# Power_Driver_2.net
KiCad netlist of a schematic drawn in Altium Designer
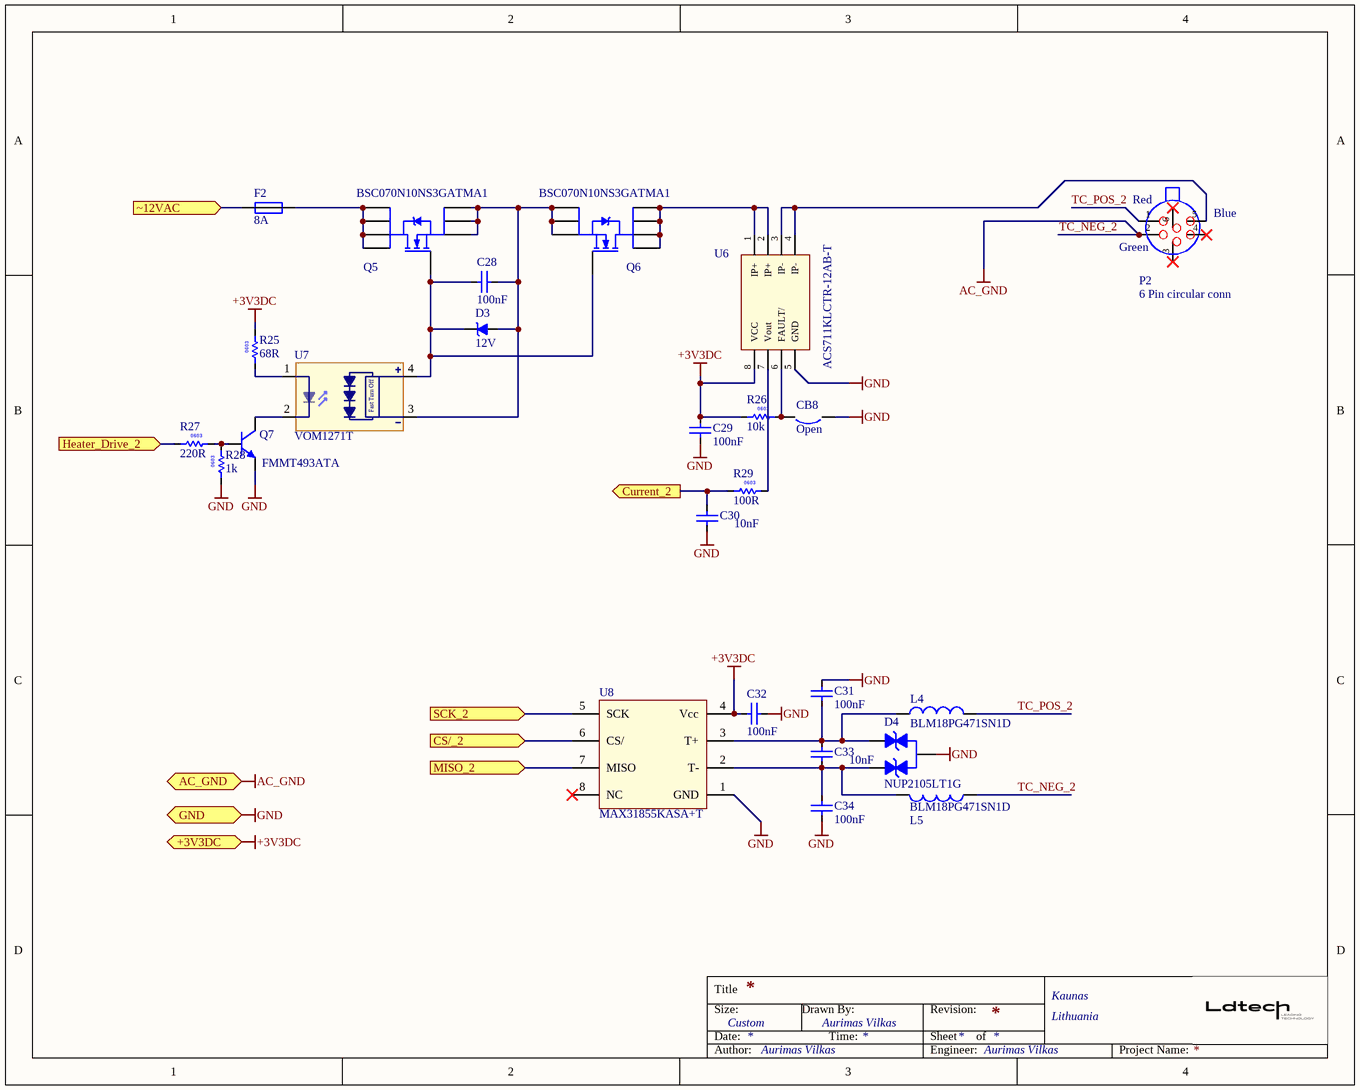
[diagram p0: Power_Driver_2.SchDoc]

(export (version "E")
  (design (tool "Eeschema 10.0.6"))
  (components
    (comp (ref "C28") (value "100nF") (footprint "CAPC1608N") (libsource (lib "DB") (part "C_SM")))
    (comp (ref "C29") (value "100nF") (footprint "CAPC1608N") (libsource (lib "DB") (part "C_SM")))
    (comp (ref "C30") (value "10nF") (footprint "CAPC1608N") (libsource (lib "DB") (part "C_SM")))
    (comp (ref "C31") (value "100nF") (footprint "CAPC1608N") (libsource (lib "DB") (part "C_SM")))
    (comp (ref "C32") (value "100nF") (footprint "CAPC1608N") (libsource (lib "DB") (part "C_SM")))
    (comp (ref "C33") (value "10nF") (footprint "CAPC1608N") (libsource (lib "DB") (part "C_SM")))
    (comp (ref "C34") (value "100nF") (footprint "CAPC1608N") (libsource (lib "DB") (part "C_SM")))
    (comp (ref "CB8")
      (value "Open")
      (footprint "CB_0603")
      (description "Circuit Breaker")
      (libsource (lib "AV_Lib_200418") (part "CB Open"))
    )
    (comp (ref "D3")
      (value "12V")
      (footprint "SOD-80C")
      (description "BZT55C12-GS08 -  Zener Single Diode, 12 V, 500 mW, SOD-80 (MiniMELF), 5 %, 2 Pins, 175 °C")
      (libsource (lib "AV_Lib_200418") (part "12V"))
    )
    (comp (ref "D4")
      (value "NUP2105LT1G")
      (footprint "SOT23-3")
      (description "NUP2105LT1G -  TVS Diode, NUP21 Series, Bidirectional, 22 V, 40 V, SOT-23, 3 Pins")
      (libsource (lib "AV_Lib_200418") (part "NUP2105LT1G"))
    )
    (comp (ref "F2")
      (value "8A")
      (footprint "1206F")
      (description "MCCFB1206TFF/8 -  Fuse, Surface Mount, 8 A, 32 V, Fast Acting, 1206")
      (libsource (lib "AV_Lib_200418") (part "8A Fuse"))
    )
    (comp (ref "L4")
      (value "BLM18PG471SN1D")
      (footprint "LL0603\\2P")
      (description "BLM18PG471SN1D -  Ferrite Bead, 0603 [1608 Metric], 470 ohm, 1 A, BLM18P Series, 0.2 ohm, ± 25%")
      (libsource (lib "DB") (part "L"))
    )
    (comp (ref "L5")
      (value "BLM18PG471SN1D")
      (footprint "LL0603\\2P")
      (description "BLM18PG471SN1D -  Ferrite Bead, 0603 [1608 Metric], 470 ohm, 1 A, BLM18P Series, 0.2 ohm, ± 25%")
      (libsource (lib "DB") (part "L"))
    )
    (comp (ref "P2")
      (value "6 Pin circular conn")
      (footprint "RPC1-12RB-6P(71)")
      (description "RPC1-12RB-6P(71) -  Circular Connector, RP Series, Panel Mount Receptacle, 6 Contacts, Solder Pin")
      (libsource (lib "AV_Lib_200418") (part "RPC1-12RB-6P(71)"))
    )
    (comp (ref "Q5")
      (value "BSC070N10NS3GATMA1")
      (footprint "PG-TDSON-8")
      (description "BSC070N10NS3GATMA1 -  Power MOSFET, N Channel, 100 V, 90 A, 0.0063 ohm, TDSON, Surface Mount")
      (libsource (lib "AV_Lib_200418") (part "BSC070N10NS3GATMA1"))
    )
    (comp (ref "Q6")
      (value "BSC070N10NS3GATMA1")
      (footprint "PG-TDSON-8")
      (description "BSC070N10NS3GATMA1 -  Power MOSFET, N Channel, 100 V, 90 A, 0.0063 ohm, TDSON, Surface Mount")
      (libsource (lib "AV_Lib_200418") (part "BSC070N10NS3GATMA1"))
    )
    (comp (ref "Q7")
      (value "FMMT493ATA")
      (footprint "SOT23-3")
      (description "FMMT493ATA -  Bipolar (BJT) Single Transistor, NPN, 60 V, 150 MHz, 500 mW, 1 A, 300 hFE")
      (libsource (lib "AV_Lib_200418") (part "FMMT493ATA"))
    )
    (comp (ref "R25") (value "68R") (footprint "RESC1608N") (libsource (lib "DB") (part "R0603")))
    (comp (ref "R26") (value "10k") (footprint "RESC1608N") (libsource (lib "DB") (part "R0603")))
    (comp (ref "R27") (value "220R") (footprint "RESC1608N") (libsource (lib "DB") (part "R0603")))
    (comp (ref "R28") (value "1k") (footprint "RESC1608N") (libsource (lib "DB") (part "R0603")))
    (comp (ref "R29") (value "100R") (footprint "RESC1608N") (libsource (lib "DB") (part "R0603")))
    (comp (ref "U6")
      (value "ACS711KLCTR-12AB-T")
      (footprint "SOIC-8")
      (description "ACS711KLCTR-12AB-T -  Current Sensor, Overcurrent Fault, 4 mA, 100 kHz, SOIC, 8 Pins, 3 V, 5.5 V")
      (libsource (lib "AV_Lib_200418") (part "ACS711KLCTR-12AB-T"))
    )
    (comp (ref "U7")
      (value "VOM1271T")
      (footprint "SOP-4")
      (libsource (lib "AV_Lib_200418") (part "VOM1271T"))
    )
    (comp (ref "U8")
      (value "MAX31855KASA+T")
      (footprint "SOIC-8")
      (libsource (lib "AV_Lib_200418") (part "MAX31855KASA+T"))
    )
  )
  (nets
    (net (code "1") (name "+3V3DC") (class "Default")
      (node (ref "C29") (pin "2") (pinfunction "2_2") (pintype "passive"))
      (node (ref "C32") (pin "1") (pinfunction "1_1") (pintype "passive"))
      (node (ref "R25") (pin "2") (pinfunction "2_2") (pintype "passive"))
      (node (ref "R26") (pin "1") (pinfunction "1_1") (pintype "passive"))
      (node (ref "U6") (pin "8") (pinfunction "VCC_8") (pintype "passive"))
      (node (ref "U8") (pin "4") (pinfunction "Vcc_4") (pintype "passive"))
    )
    (net (code "2") (name "/CS{slash}_2") (class "Default")
      (node (ref "U8") (pin "6") (pinfunction "CS/_6") (pintype "passive"))
    )
    (net (code "3") (name "/Current_2") (class "Default")
      (node (ref "C30") (pin "1") (pinfunction "1_1") (pintype "passive"))
      (node (ref "R29") (pin "1") (pinfunction "1_1") (pintype "passive"))
    )
    (net (code "4") (name "/Heater_Drive_2") (class "Default")
      (node (ref "R27") (pin "1") (pinfunction "1_1") (pintype "passive"))
    )
    (net (code "5") (name "/MISO_2") (class "Default")
      (node (ref "U8") (pin "7") (pinfunction "MISO_7") (pintype "passive"))
    )
    (net (code "6") (name "/SCK_2") (class "Default")
      (node (ref "U8") (pin "5") (pinfunction "SCK_5") (pintype "passive"))
    )
    (net (code "7") (name "/TC_POS_2") (class "Default")
      (node (ref "L4") (pin "2") (pinfunction "2_2") (pintype "passive"))
      (node (ref "P2") (pin "1") (pinfunction "1_1") (pintype "passive"))
    )
    (net (code "8") (name "/~12VAC") (class "Default")
      (node (ref "F2") (pin "2") (pinfunction "2_2") (pintype "passive"))
    )
    (net (code "9") (name "AC_GND") (class "Default")
      (node (ref "L5") (pin "1") (pinfunction "1_1") (pintype "passive"))
      (node (ref "P2") (pin "2") (pinfunction "2_2") (pintype "passive"))
    )
    (net (code "10") (name "GND") (class "Default")
      (node (ref "C29") (pin "1") (pinfunction "1_1") (pintype "passive"))
      (node (ref "C30") (pin "2") (pinfunction "2_2") (pintype "passive"))
      (node (ref "C31") (pin "2") (pinfunction "2_2") (pintype "passive"))
      (node (ref "C32") (pin "2") (pinfunction "2_2") (pintype "passive"))
      (node (ref "C34") (pin "1") (pinfunction "1_1") (pintype "passive"))
      (node (ref "CB8") (pin "1") (pinfunction "1_1") (pintype "passive"))
      (node (ref "D4") (pin "3") (pinfunction "3_3") (pintype "passive"))
      (node (ref "Q7") (pin "2") (pinfunction "E_2") (pintype "passive"))
      (node (ref "R28") (pin "1") (pinfunction "1_1") (pintype "passive"))
      (node (ref "U6") (pin "5") (pinfunction "GND_5") (pintype "passive"))
      (node (ref "U8") (pin "1") (pinfunction "GND_1") (pintype "passive"))
    )
    (net (code "11") (name "Net-(D3-A)") (class "Default")
      (node (ref "C28") (pin "1") (pinfunction "1_1") (pintype "passive"))
      (node (ref "D3") (pin "2") (pinfunction "A_2") (pintype "passive"))
      (node (ref "Q5") (pin "3") (pinfunction "S_3") (pintype "passive"))
      (node (ref "Q6") (pin "3") (pinfunction "S_3") (pintype "passive"))
      (node (ref "U7") (pin "3") (pinfunction "K_3") (pintype "passive"))
    )
    (net (code "12") (name "Net-(D3-K)") (class "Default")
      (node (ref "C28") (pin "2") (pinfunction "2_2") (pintype "passive"))
      (node (ref "D3") (pin "1") (pinfunction "K_1") (pintype "passive"))
      (node (ref "Q5") (pin "1") (pinfunction "G_1") (pintype "passive"))
      (node (ref "Q6") (pin "1") (pinfunction "G_1") (pintype "passive"))
      (node (ref "U7") (pin "4") (pinfunction "E_4") (pintype "passive"))
    )
    (net (code "13") (name "Net-(P2-Pad5)") (class "Default")
      (node (ref "P2") (pin "5") (pinfunction "5_5") (pintype "passive"))
      (node (ref "U6") (pin "3") (pinfunction "IP-_3") (pintype "passive"))
      (node (ref "U6") (pin "4") (pinfunction "IP-_4") (pintype "passive"))
    )
    (net (code "14") (name "Net-(Q5-D)") (class "Default")
      (node (ref "F2") (pin "1") (pinfunction "1_1") (pintype "passive"))
      (node (ref "Q5") (pin "2") (pinfunction "D_2") (pintype "passive"))
    )
    (net (code "15") (name "Net-(Q6-D)") (class "Default")
      (node (ref "Q6") (pin "2") (pinfunction "D_2") (pintype "passive"))
      (node (ref "U6") (pin "1") (pinfunction "IP+_1") (pintype "passive"))
      (node (ref "U6") (pin "2") (pinfunction "IP+_2") (pintype "passive"))
    )
    (net (code "16") (name "Net-(Q7-B)") (class "Default")
      (node (ref "Q7") (pin "1") (pinfunction "B_1") (pintype "passive"))
      (node (ref "R27") (pin "2") (pinfunction "2_2") (pintype "passive"))
      (node (ref "R28") (pin "2") (pinfunction "2_2") (pintype "passive"))
    )
    (net (code "17") (name "Net-(Q7-C)") (class "Default")
      (node (ref "Q7") (pin "3") (pinfunction "C_3") (pintype "passive"))
      (node (ref "U7") (pin "2") (pinfunction "K_2") (pintype "passive"))
    )
    (net (code "18") (name "Net-(U6-FAULT{slash})") (class "Default")
      (node (ref "CB8") (pin "2") (pinfunction "2_2") (pintype "passive"))
      (node (ref "R26") (pin "2") (pinfunction "2_2") (pintype "passive"))
      (node (ref "U6") (pin "6") (pinfunction "FAULT/_6") (pintype "passive"))
    )
    (net (code "19") (name "Net-(U6-Vout)") (class "Default")
      (node (ref "R29") (pin "2") (pinfunction "2_2") (pintype "passive"))
      (node (ref "U6") (pin "7") (pinfunction "Vout_7") (pintype "passive"))
    )
    (net (code "20") (name "Net-(U7-A)") (class "Default")
      (node (ref "R25") (pin "1") (pinfunction "1_1") (pintype "passive"))
      (node (ref "U7") (pin "1") (pinfunction "A_1") (pintype "passive"))
    )
    (net (code "21") (name "Net-(U8-T+)") (class "Default")
      (node (ref "C31") (pin "1") (pinfunction "1_1") (pintype "passive"))
      (node (ref "C33") (pin "1") (pinfunction "1_1") (pintype "passive"))
      (node (ref "D4") (pin "2") (pinfunction "2_2") (pintype "passive"))
      (node (ref "L4") (pin "1") (pinfunction "1_1") (pintype "passive"))
      (node (ref "U8") (pin "3") (pinfunction "T+_3") (pintype "passive"))
    )
    (net (code "22") (name "Net-(U8-T-)") (class "Default")
      (node (ref "C33") (pin "2") (pinfunction "2_2") (pintype "passive"))
      (node (ref "C34") (pin "2") (pinfunction "2_2") (pintype "passive"))
      (node (ref "D4") (pin "1") (pinfunction "1_1") (pintype "passive"))
      (node (ref "L5") (pin "2") (pinfunction "2_2") (pintype "passive"))
      (node (ref "U8") (pin "2") (pinfunction "T-_2") (pintype "passive"))
    )
    (net (code "23") (name "unconnected-(P2-Pad3)") (class "Default")
      (node (ref "P2") (pin "3") (pinfunction "3_3") (pintype "passive+no_connect"))
    )
    (net (code "24") (name "unconnected-(P2-Pad4)") (class "Default")
      (node (ref "P2") (pin "4") (pinfunction "4_4") (pintype "passive+no_connect"))
    )
    (net (code "25") (name "unconnected-(P2-Pad6)") (class "Default")
      (node (ref "P2") (pin "6") (pinfunction "6_6") (pintype "passive+no_connect"))
    )
    (net (code "26") (name "unconnected-(U8-NC-Pad8)") (class "Default")
      (node (ref "U8") (pin "8") (pinfunction "NC_8") (pintype "passive+no_connect"))
    )
  )
)
